# BQ25890_Battery_Charger.net
KiCad netlist of a schematic drawn in Altium Designer
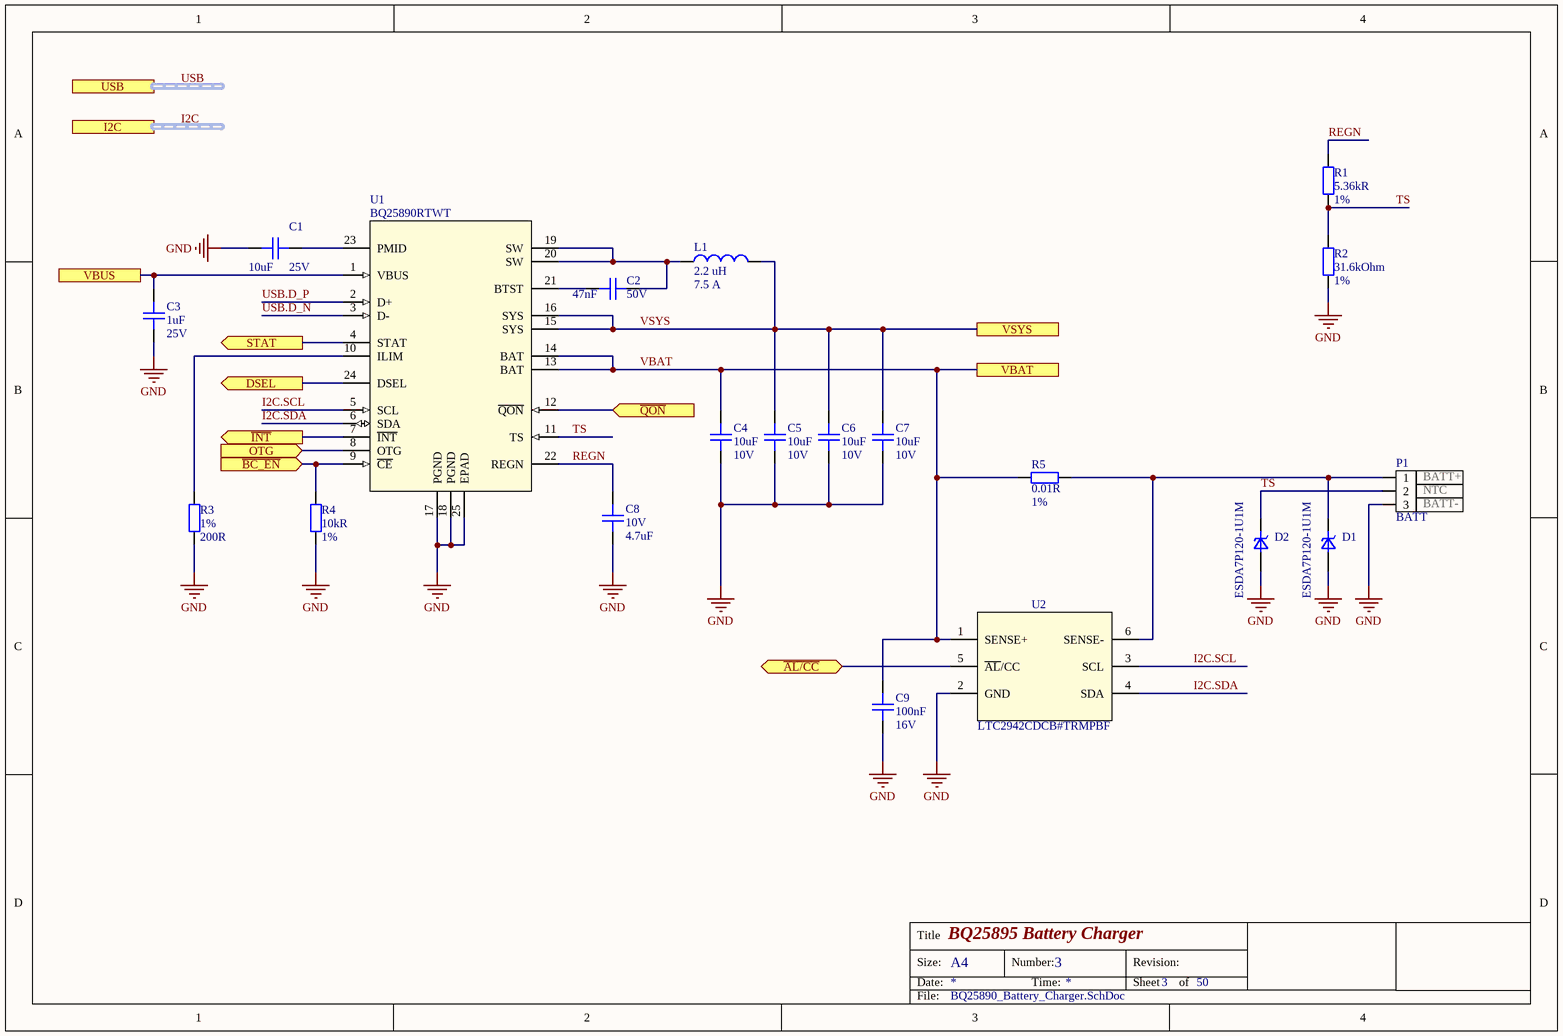
[diagram p0: BQ25890_Battery_Charger.SchDoc]

(export (version "E")
  (design (tool "Eeschema 10.0.6"))
  (components
    (comp (ref "C1")
      (value "CAP CER 10UF 25V X7R 1206")
      (footprint "C1206")
      (description "10µF ±10% 25V Ceramic Capacitor X7R 1206 (3216 Metric)")
      (fields
        (field (name "MANUFACTURER") "Yageo")
        (field (name "MANUFACTURER PART NUMBER") "CC1206KKX7R8BB106")
        (field (name "CAPACITANCE") "10uF")
        (field (name "VOLTAGE RATING") "25V")
      )
      (libsource (lib "Control_Board_Model") (part "CAP CER 10UF 25V X7R 1206"))
    )
    (comp (ref "C2")
      (value "CAP CER 0.047UF 50V X7R 0402")
      (footprint "C0402")
      (description "0.047µF ±10% 50V Ceramic Capacitor X7R 0402 (1005 Metric)")
      (fields
        (field (name "MANUFACTURER") "TDK")
        (field (name "MANUFACTURER PART NUMBER") "CGA2B3X7R1H473K050BB")
        (field (name "CAPACITANCE") "47nF")
        (field (name "VOLTAGE RATING") "50V")
      )
      (libsource (lib "capacitors_smd") (part "CAP CER 0.047UF 50V X7R 0402"))
    )
    (comp (ref "C3")
      (value "CAP CER 1UF 25V X7R 0805")
      (footprint "C0805")
      (description "1 µF ±10% 25V Ceramic Capacitor X7R 0805 (2012 Metric)")
      (fields
        (field (name "MANUFACTURER") "Yageo")
        (field (name "MANUFACTURER PART NUMBER") "CC0805KKX7R8BB105")
        (field (name "CAPACITANCE") "1uF")
        (field (name "VOLTAGE RATING") "25V")
      )
      (libsource (lib "Control_Board_Model") (part "CAP CER 1UF 25V X7R 0805"))
    )
    (comp (ref "C4")
      (value "CAP CER 10uF X7R 10% 0805")
      (footprint "C0805")
      (description "Capacitor,10uF,10V,X7R,10%,0805,Murata")
      (fields
        (field (name "MANUFACTURER") "Murata")
        (field (name "MANUFACTURER PART NUMBER") "GRM21BR71A106KA73L")
        (field (name "CAPACITANCE") "10uF")
        (field (name "VOLTAGE RATING") "10V")
      )
      (libsource (lib "capacitors_smd") (part "CAP CER 10uF X7R 10% 0805"))
    )
    (comp (ref "C5")
      (value "CAP CER 10uF X7R 10% 0805")
      (footprint "C0805")
      (description "Capacitor,10uF,10V,X7R,10%,0805,Murata")
      (fields
        (field (name "MANUFACTURER") "Murata")
        (field (name "MANUFACTURER PART NUMBER") "GRM21BR71A106KA73L")
        (field (name "CAPACITANCE") "10uF")
        (field (name "VOLTAGE RATING") "10V")
      )
      (libsource (lib "capacitors_smd") (part "CAP CER 10uF X7R 10% 0805"))
    )
    (comp (ref "C6")
      (value "CAP CER 10uF X7R 10% 0805")
      (footprint "C0805")
      (description "Capacitor,10uF,10V,X7R,10%,0805,Murata")
      (fields
        (field (name "MANUFACTURER") "Murata")
        (field (name "MANUFACTURER PART NUMBER") "GRM21BR71A106KA73L")
        (field (name "CAPACITANCE") "10uF")
        (field (name "VOLTAGE RATING") "10V")
      )
      (libsource (lib "capacitors_smd") (part "CAP CER 10uF X7R 10% 0805"))
    )
    (comp (ref "C7")
      (value "CAP CER 10uF X7R 10% 0805")
      (footprint "C0805")
      (description "Capacitor,10uF,10V,X7R,10%,0805,Murata")
      (fields
        (field (name "MANUFACTURER") "Murata")
        (field (name "MANUFACTURER PART NUMBER") "GRM21BR71A106KA73L")
        (field (name "CAPACITANCE") "10uF")
        (field (name "VOLTAGE RATING") "10V")
      )
      (libsource (lib "capacitors_smd") (part "CAP CER 10uF X7R 10% 0805"))
    )
    (comp (ref "C8")
      (value "CAP CER 4.7UF 10V X5R 0603")
      (footprint "C0603")
      (description "4.7µF ±10% 10V Ceramic Capacitor X5R 0603 (1608 Metric)")
      (fields
        (field (name "MANUFACTURER") "Yageo")
        (field (name "MANUFACTURER PART NUMBER") "CC0603KRX5R6BB475")
        (field (name "VOLTAGE RATING") "10V")
        (field (name "CAPACITANCE") "4.7uF")
      )
      (libsource (lib "capacitors_smd") (part "CAP CER 4.7UF 10V X5R 0603"))
    )
    (comp (ref "C9")
      (value "CAP CER 0.1UF 16V X7R 0402")
      (footprint "C0402")
      (description "0.1µF ±10% 16V Ceramic Capacitor X7R 0402 (1005 Metric)")
      (fields
        (field (name "MANUFACTURER PART NUMBER") "CC0402KRX7R7BB104")
        (field (name "MANUFACTURER") "Yageo")
        (field (name "CAPACITANCE") "100nF")
        (field (name "VOLTAGE") "16V")
      )
      (libsource (lib "Control_Board_Model") (part "CAP CER 0.1UF 16V X7R 0402"))
    )
    (comp (ref "D1")
      (value "ESDA7P120-1U1M")
      (footprint "ST_QFN_1610")
      (description "11.5V Clamp 120A (8/20µs) Ipp Tvs Diode Surface Mount 1610")
      (fields (field (name "MANUFACTURER") "STMicroelectronics"))
      (libsource (lib "diodes_tvs") (part "TVS DIODE ESDA7P120-1U1M 5.5V 11.5V 1610"))
    )
    (comp (ref "D2")
      (value "ESDA7P120-1U1M")
      (footprint "ST_QFN_1610")
      (description "11.5V Clamp 120A (8/20µs) Ipp Tvs Diode Surface Mount 1610")
      (fields (field (name "MANUFACTURER") "STMicroelectronics"))
      (libsource (lib "diodes_tvs") (part "TVS DIODE ESDA7P120-1U1M 5.5V 11.5V 1610"))
    )
    (comp (ref "L1")
      (value "FIXED IND 2.2UH 7.5A 16.1MOHM SM")
      (footprint "IND_WE_MAPI")
      (description "2.2 µH Shielded - Inductor 7.5 A 16.1mOhm Max Nonstandard -")
      (fields
        (field (name "MANUFACTURER") "Wurth Elektronik")
        (field (name "MANUFACTURER PART NUMBER") "74438367022")
        (field (name "INDUCTANCE") "2.2 uH")
        (field (name "MAXIMUM DC CURRENT") "7.5 A")
      )
      (libsource (lib "Control_Board_Model") (part "FIXED IND 2.2UH 7.5A 16.1MOHM SM"))
    )
    (comp (ref "P1")
      (value "BATT")
      (footprint "CONN_JST_BM03B-AUHKS-GA-TB(LF)(SN)")
      (description "Connector Header Surface Mount, Right Angle 3 position")
      (fields
        (field (name "MANUFACTURER") "JST")
        (field (name "MANUFACTURER PART NUMBER") "BM03B-AUHKS-GA-TB(LF)(SN)")
        (field (name "PIN_1") "BATT+")
        (field (name "PIN_2") "NTC")
        (field (name "PIN_3") "BATT-")
      )
      (libsource (lib "Control_Board_Model") (part "CONN HEADER SMD R/A 3POS"))
    )
    (comp (ref "R1")
      (value "RES SMD 5.36K OHM 1% 1/16W 0402")
      (footprint "R0402")
      (description "5.36 kOhms ±1% 0.063W, 1/16W Chip Resistor 0402 (1005 Metric) Moisture Resistant Thick Film")
      (fields
        (field (name "MANUFACTURER PART NUMBER") "RC0402FR-075K36L")
        (field (name "MANUFACTURER") "Yageo")
        (field (name "RESISTANCE") "5.36kR")
        (field (name "TOLERANCE") "1%")
      )
      (libsource (lib "resistors_smd") (part "RES SMD 5.36K OHM 1% 1/16W 0402"))
    )
    (comp (ref "R2")
      (value "RES SMD 31.6K OHM 1% 1/16W 0402")
      (footprint "R0402")
      (description "31.6 kOhms ±1% 0.063W, 1/16W Chip Resistor 0402 (1005 Metric) Moisture Resistant Thick Film")
      (fields
        (field (name "MANUFACTURER PART NUMBER") "RC0402FR-0731K6L")
        (field (name "MANUFACTURER") "Yageo")
        (field (name "RESISTANCE") "31.6kOhm")
        (field (name "TOLERANCE") "1%")
      )
      (libsource (lib "resistors_smd") (part "RES SMD 31.6K OHM 1% 1/16W 0402"))
    )
    (comp (ref "R3")
      (value "RES SMD 200 OHM 1% 1/16W 0402")
      (footprint "R0402")
      (description "200 Ohms ±1% 0.063W, 1/16W Chip Resistor 0402 (1005 Metric) Moisture Resistant Thick Film")
      (fields
        (field (name "MANUFACTURER") "Yageo")
        (field (name "MANUFACTURER PART NUMBER") "RC0402FR-07200RP")
        (field (name "TOLERANCE") "1%")
        (field (name "RESISTANCE") "200R")
      )
      (libsource (lib "Control_Board_Model") (part "RES SMD 200 OHM 1% 1/16W 0402"))
    )
    (comp (ref "R4")
      (value "RES SMD 10K OHM 1% 1/16W 0402")
      (footprint "R0402")
      (description "10 kOhms ±1% 0.063W, 1/16W Chip Resistor 0402 (1005 Metric) Moisture Resistant Thick Film")
      (fields
        (field (name "MANUFACTURER PART NUMBER") "RC0402FR-0710KP")
        (field (name "MANUFACTURER") "Yageo")
        (field (name "RESISTANCE") "10kR")
        (field (name "TOLERANCE") "1%")
      )
      (libsource (lib "resistors_smd") (part "RES SMD 10K OHM 1% 1/16W 0402"))
    )
    (comp (ref "R5")
      (value "RES 0.01 OHM 1% 1/2W 1206")
      (footprint "R1206")
      (fields
        (field (name "MANUFACTURER") "Yageo")
        (field (name "MANUFACTURER PART NUMBER") "PE1206FRF7W0R01L")
        (field (name "RESISTANCE") "0.01R")
        (field (name "TOLERANCE") "1%")
      )
      (libsource (lib "Control_Board_Model") (part "RES 0.01 OHM 1% 1/2W 1206"))
    )
    (comp (ref "U1")
      (value "BQ25890RTWT")
      (footprint "WQFN-24")
      (description "Charger IC Lithium Ion/Polymer 24WQFN")
      (fields (field (name "MANUFACTURER") "Texas Instruments"))
      (libsource (lib "Control_Board_Model") (part "IC BQ25890RTWT BATT CHG LI-ION 1CELL 24WQFN"))
    )
    (comp (ref "U2")
      (value "LTC2942CDCB#TRMPBF")
      (footprint "DFN6")
      (description "Battery Battery Monitor IC Lithium Ion 6-DFN (2x3)")
      (fields (field (name "MANUFACTURER") "Analog Devices Inc."))
      (libsource (lib "Control_Board_Model") (part "IC LTC2942 BATT MON LI-ION 1CELL 6DFN"))
    )
  )
  (nets
    (net (code "3") (name "/AL{slash}CC") (class "Default")
      (node (ref "U2") (pin "5") (pinfunction "~{AL}/CC_5") (pintype "passive"))
    )
    (net (code "4") (name "/BC_EN") (class "Default")
      (node (ref "R4") (pin "1") (pinfunction "1_1") (pintype "passive"))
      (node (ref "U1") (pin "9") (pinfunction "~{CE}_9") (pintype "input"))
    )
    (net (code "5") (name "/DSEL") (class "Default")
      (node (ref "U1") (pin "24") (pinfunction "DSEL_24") (pintype "passive"))
    )
    (net (code "6") (name "/I2C.SCL") (class "Default")
      (node (ref "U1") (pin "5") (pinfunction "SCL_5") (pintype "input"))
      (node (ref "U2") (pin "3") (pinfunction "SCL_3") (pintype "passive"))
    )
    (net (code "7") (name "/I2C.SDA") (class "Default")
      (node (ref "U1") (pin "6") (pinfunction "SDA_6") (pintype "bidirectional"))
      (node (ref "U2") (pin "4") (pinfunction "SDA_4") (pintype "passive"))
    )
    (net (code "8") (name "/INT") (class "Default")
      (node (ref "U1") (pin "7") (pinfunction "INT_7") (pintype "open_collector"))
    )
    (net (code "9") (name "/OTG") (class "Default")
      (node (ref "U1") (pin "8") (pinfunction "OTG_8") (pintype "passive"))
    )
    (net (code "10") (name "/QON") (class "Default")
      (node (ref "U1") (pin "12") (pinfunction "~{QON}_12") (pintype "input"))
    )
    (net (code "11") (name "/REGN") (class "Default")
      (node (ref "C8") (pin "2") (pinfunction "2_2") (pintype "passive"))
      (node (ref "R1") (pin "1") (pinfunction "1_1") (pintype "passive"))
      (node (ref "U1") (pin "22") (pinfunction "REGN_22") (pintype "power_in"))
    )
    (net (code "12") (name "/STAT") (class "Default")
      (node (ref "U1") (pin "4") (pinfunction "STAT_4") (pintype "open_collector"))
    )
    (net (code "13") (name "/TS") (class "Default")
      (node (ref "D2") (pin "1") (pinfunction "K_1") (pintype "passive"))
      (node (ref "P1") (pin "2") (pinfunction "2_2") (pintype "passive"))
      (node (ref "R1") (pin "2") (pinfunction "2_2") (pintype "passive"))
      (node (ref "R2") (pin "2") (pinfunction "2_2") (pintype "passive"))
      (node (ref "U1") (pin "11") (pinfunction "TS_11") (pintype "input"))
    )
    (net (code "14") (name "/USB.D_N") (class "Default")
      (node (ref "U1") (pin "3") (pinfunction "D-_3") (pintype "input"))
    )
    (net (code "15") (name "/USB.D_P") (class "Default")
      (node (ref "U1") (pin "2") (pinfunction "D+_2") (pintype "input"))
    )
    (net (code "16") (name "/VBAT") (class "Default")
      (node (ref "C4") (pin "2") (pinfunction "2_2") (pintype "passive"))
      (node (ref "C9") (pin "2") (pinfunction "2_2") (pintype "passive"))
      (node (ref "R5") (pin "1") (pinfunction "1_1") (pintype "passive"))
      (node (ref "U1") (pin "13") (pinfunction "BAT_13") (pintype "power_in"))
      (node (ref "U1") (pin "14") (pinfunction "BAT_14") (pintype "power_in"))
      (node (ref "U2") (pin "1") (pinfunction "SENSE+_1") (pintype "passive"))
    )
    (net (code "17") (name "/VBUS") (class "Default")
      (node (ref "C3") (pin "1") (pinfunction "1_1") (pintype "passive"))
      (node (ref "U1") (pin "1") (pinfunction "VBUS_1") (pintype "input"))
    )
    (net (code "18") (name "/VSYS") (class "Default")
      (node (ref "C5") (pin "2") (pinfunction "2_2") (pintype "passive"))
      (node (ref "C6") (pin "2") (pinfunction "2_2") (pintype "passive"))
      (node (ref "C7") (pin "2") (pinfunction "2_2") (pintype "passive"))
      (node (ref "L1") (pin "2") (pinfunction "2_2") (pintype "passive"))
      (node (ref "U1") (pin "15") (pinfunction "SYS_15") (pintype "power_in"))
      (node (ref "U1") (pin "16") (pinfunction "SYS_16") (pintype "power_in"))
    )
    (net (code "21") (name "GND") (class "Default")
      (node (ref "C1") (pin "1") (pinfunction "1_1") (pintype "passive"))
      (node (ref "C3") (pin "2") (pinfunction "2_2") (pintype "passive"))
      (node (ref "C4") (pin "1") (pinfunction "1_1") (pintype "passive"))
      (node (ref "C5") (pin "1") (pinfunction "1_1") (pintype "passive"))
      (node (ref "C6") (pin "1") (pinfunction "1_1") (pintype "passive"))
      (node (ref "C7") (pin "1") (pinfunction "1_1") (pintype "passive"))
      (node (ref "C8") (pin "1") (pinfunction "1_1") (pintype "passive"))
      (node (ref "C9") (pin "1") (pinfunction "1_1") (pintype "passive"))
      (node (ref "D1") (pin "2") (pinfunction "A_2") (pintype "passive"))
      (node (ref "D2") (pin "2") (pinfunction "A_2") (pintype "passive"))
      (node (ref "P1") (pin "3") (pinfunction "3_3") (pintype "passive"))
      (node (ref "R2") (pin "1") (pinfunction "1_1") (pintype "passive"))
      (node (ref "R3") (pin "2") (pinfunction "2_2") (pintype "passive"))
      (node (ref "R4") (pin "2") (pinfunction "2_2") (pintype "passive"))
      (node (ref "U1") (pin "17") (pinfunction "PGND_17") (pintype "power_in"))
      (node (ref "U1") (pin "18") (pinfunction "PGND_18") (pintype "power_in"))
      (node (ref "U1") (pin "25") (pinfunction "EPAD_25") (pintype "power_in"))
      (node (ref "U2") (pin "2") (pinfunction "GND_2") (pintype "passive"))
    )
    (net (code "22") (name "Net-(C2-Pad2)") (class "Default")
      (node (ref "C2") (pin "2") (pinfunction "2_2") (pintype "passive"))
      (node (ref "L1") (pin "1") (pinfunction "1_1") (pintype "passive"))
      (node (ref "U1") (pin "19") (pinfunction "SW_19") (pintype "power_in"))
      (node (ref "U1") (pin "20") (pinfunction "SW_20") (pintype "power_in"))
    )
    (net (code "23") (name "Net-(D1-K)") (class "Default")
      (node (ref "D1") (pin "1") (pinfunction "K_1") (pintype "passive"))
      (node (ref "P1") (pin "1") (pinfunction "1_1") (pintype "passive"))
      (node (ref "R5") (pin "2") (pinfunction "2_2") (pintype "passive"))
      (node (ref "U2") (pin "6") (pinfunction "SENSE-_6") (pintype "passive"))
    )
    (net (code "24") (name "Net-(U1-BTST)") (class "Default")
      (node (ref "C2") (pin "1") (pinfunction "1_1") (pintype "passive"))
      (node (ref "U1") (pin "21") (pinfunction "BTST_21") (pintype "power_in"))
    )
    (net (code "25") (name "Net-(U1-ILIM)") (class "Default")
      (node (ref "R3") (pin "1") (pinfunction "1_1") (pintype "passive"))
      (node (ref "U1") (pin "10") (pinfunction "ILIM_10") (pintype "passive"))
    )
    (net (code "26") (name "Net-(U1-PMID)") (class "Default")
      (node (ref "C1") (pin "2") (pinfunction "2_2") (pintype "passive"))
      (node (ref "U1") (pin "23") (pinfunction "PMID_23") (pintype "power_in"))
    )
  )
)
